# SCH_HackerCardnew_2025-03-30.net
KiCad netlist of a schematic drawn in EasyEDA
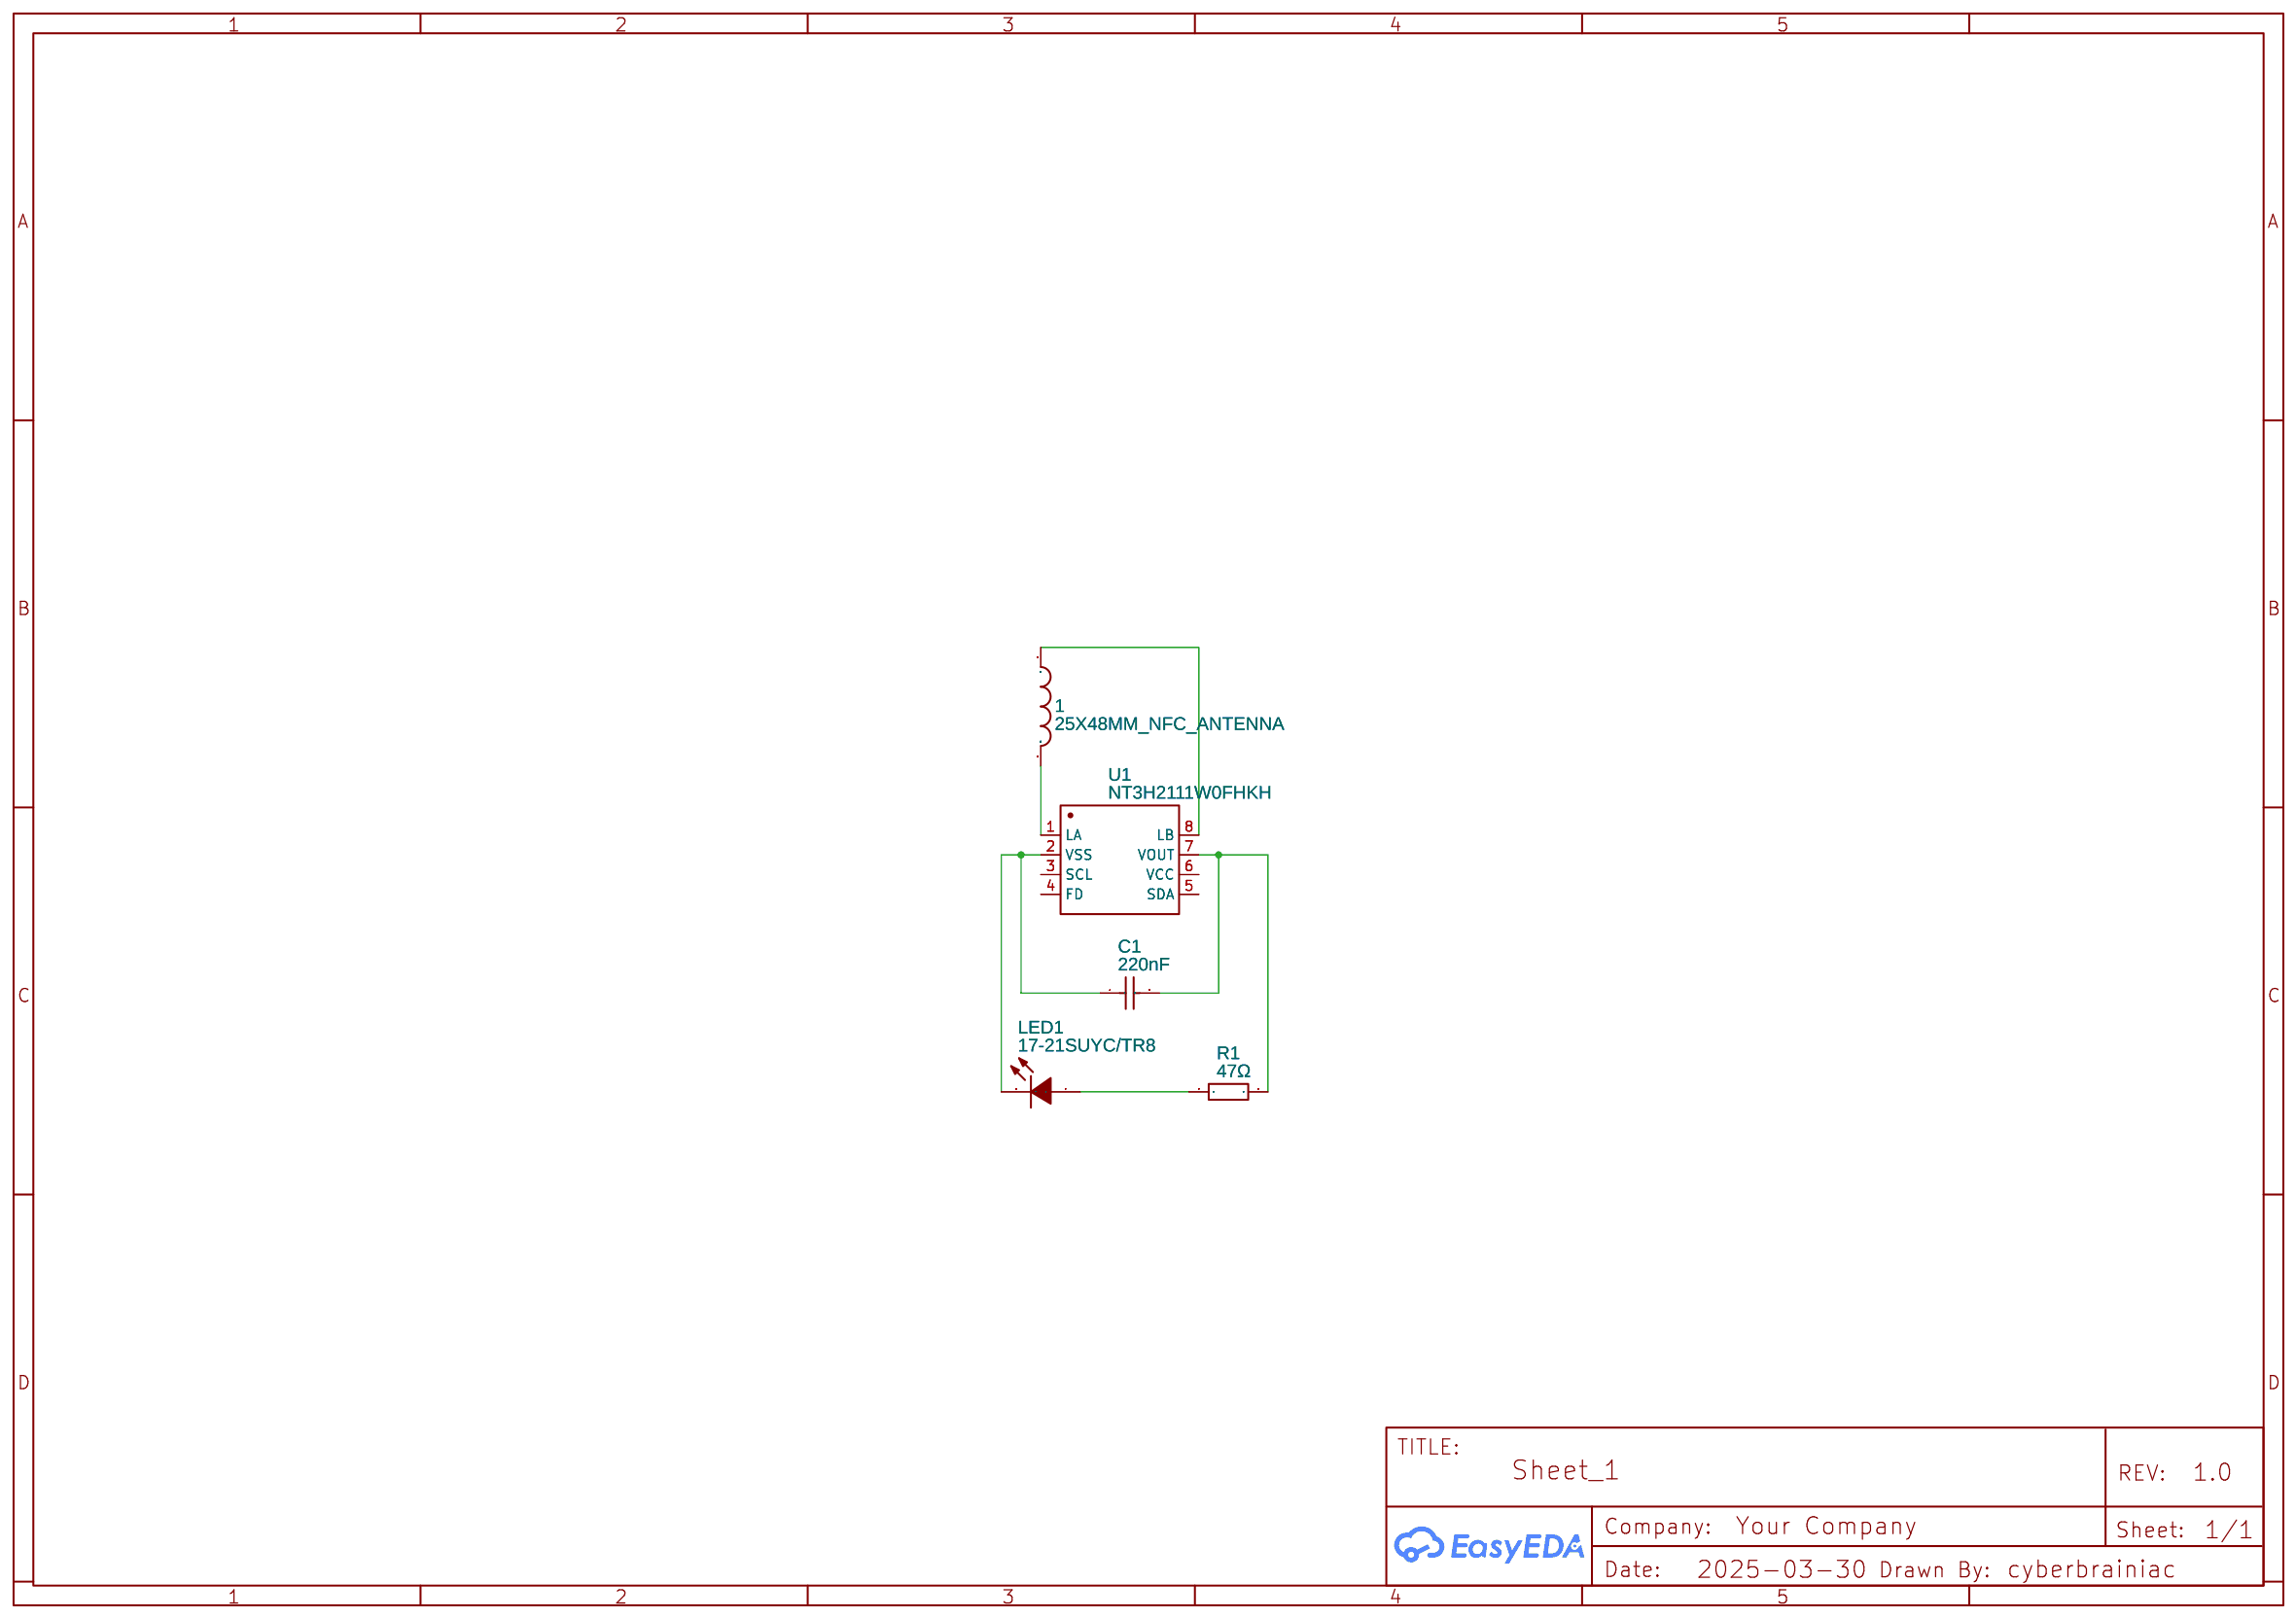
[diagram p0: schematic sheet]

(export (version "E")
  (design (tool "Eeschema 10.0.6"))
  (components
    (comp (ref "1") (value "25X48MM_NFC_ANTENNA") (libsource (lib "") (part "25X48MM_NFC_ANTENNA")))
    (comp (ref "C1")
      (value "220nF")
      (fields
        (field (name "Manufacturer Part") "CL10B224KB8NNNC")
        (field (name "Manufacturer") "SAMSUNG(三星)")
      )
      (libsource (lib "") (part "CL10B224KB8NNNC"))
    )
    (comp (ref "LED1")
      (value "17-21SUYC/TR8")
      (fields (field (name "Manufacturer Part") "KT-0805黄灯") (field (name "Manufacturer") "KENTO"))
      (libsource (lib "") (part "17-21SUYC/TR8"))
    )
    (comp (ref "R1")
      (value "47Ω")
      (fields
        (field (name "Manufacturer Part") "0603WAF470JT5E")
        (field (name "Manufacturer") "UNI-ROYAL(厚声)")
      )
      (libsource (lib "") (part "0603WAF470JT5E"))
    )
    (comp (ref "U1")
      (value "NT3H2111W0FHKH")
      (fields (field (name "Manufacturer") "NXP(恩智浦)"))
      (libsource (lib "") (part "NT3H2111W0FHKH"))
    )
  )
  (nets
    (net (code "1") (name "Net-(LED1-+)") (class "Default")
      (node (ref "LED1") (pin "1") (pinfunction "+_1") (pintype "unspecified"))
      (node (ref "R1") (pin "1") (pinfunction "1_1") (pintype "input"))
    )
    (net (code "2") (name "Net-(LED1--)") (class "Default")
      (node (ref "C1") (pin "1") (pinfunction "1_1") (pintype "input"))
      (node (ref "LED1") (pin "2") (pinfunction "-_2") (pintype "unspecified"))
      (node (ref "U1") (pin "2") (pinfunction "VSS_2") (pintype "unspecified"))
    )
    (net (code "3") (name "Net-(U1-LA)") (class "Default")
      (node (ref "1") (pin "P$2") (pinfunction "P$2_P$2") (pintype "bidirectional"))
      (node (ref "U1") (pin "1") (pinfunction "LA_1") (pintype "unspecified"))
    )
    (net (code "4") (name "Net-(U1-LB)") (class "Default")
      (node (ref "1") (pin "P$1") (pinfunction "P$1_P$1") (pintype "bidirectional"))
      (node (ref "U1") (pin "8") (pinfunction "LB_8") (pintype "unspecified"))
    )
    (net (code "5") (name "Net-(U1-VOUT)") (class "Default")
      (node (ref "C1") (pin "2") (pinfunction "2_2") (pintype "input"))
      (node (ref "R1") (pin "2") (pinfunction "2_2") (pintype "input"))
      (node (ref "U1") (pin "7") (pinfunction "VOUT_7") (pintype "unspecified"))
    )
    (net (code "6") (name "unconnected-(U1-FD-Pad4)") (class "Default")
      (node (ref "U1") (pin "4") (pinfunction "FD_4") (pintype "unspecified"))
    )
    (net (code "7") (name "unconnected-(U1-SCL-Pad3)") (class "Default")
      (node (ref "U1") (pin "3") (pinfunction "SCL_3") (pintype "unspecified"))
    )
    (net (code "8") (name "unconnected-(U1-SDA-Pad5)") (class "Default")
      (node (ref "U1") (pin "5") (pinfunction "SDA_5") (pintype "unspecified"))
    )
    (net (code "9") (name "unconnected-(U1-VCC-Pad6)") (class "Default")
      (node (ref "U1") (pin "6") (pinfunction "VCC_6") (pintype "unspecified"))
    )
  )
)
